# 01-POWER.net
KiCad netlist of a schematic drawn in Altium Designer
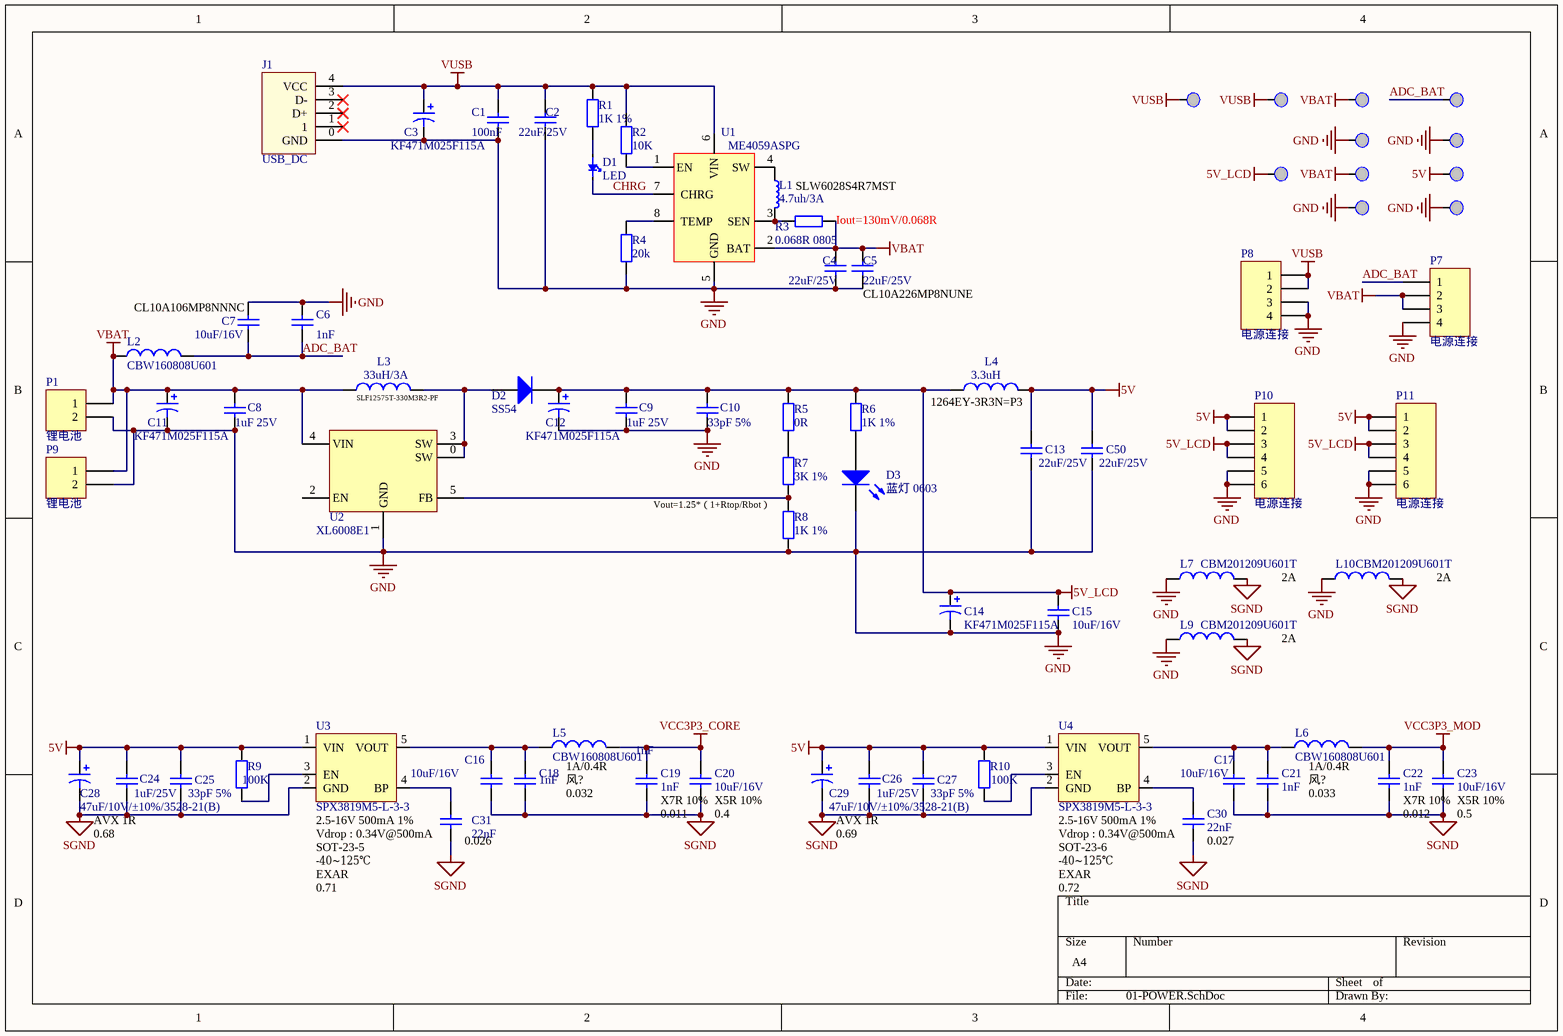
[diagram p0: 01-POWER.SchDoc]

(export (version "E")
  (design (tool "Eeschema 10.0.6"))
  (components
    (comp (ref "C1")
      (value "100nF")
      (footprint "C1608(CC0603)")
      (description "Capacitor")
      (fields (field (name "PUBLISHER") "Altium Limited"))
      (libsource (lib "Miscellaneous Devices") (part "Cap"))
    )
    (comp (ref "C2")
      (value "22uF/25V")
      (footprint "C2012(CC0805)")
      (description "Capacitor")
      (fields (field (name "PUBLISHER") "Altium Limited"))
      (libsource (lib "Miscellaneous Devices") (part "Cap"))
    )
    (comp (ref "C3")
      (value "KF471M025F115A")
      (footprint "RB.3.5/.8mm")
      (description "Polarized Capacitor (Radial)")
      (fields (field (name "PUBLISHER") "Altium Limited"))
      (libsource (lib "Miscellaneous Devices") (part "Cap Pol1"))
    )
    (comp (ref "C4")
      (value "22uF/25V")
      (footprint "C2012(CC0805)")
      (description "Capacitor")
      (fields (field (name "PUBLISHER") "Altium Limited"))
      (libsource (lib "Miscellaneous Devices") (part "Cap"))
    )
    (comp (ref "C5")
      (value "22uF/25V")
      (footprint "C2012(CC0805)")
      (description "Capacitor")
      (fields (field (name "PUBLISHER") "Altium Limited"))
      (libsource (lib "Miscellaneous Devices") (part "Cap"))
    )
    (comp (ref "C6")
      (value "1nF")
      (footprint "C1608(CC0603)")
      (description "Capacitor")
      (fields (field (name "PUBLISHER") "Altium Limited"))
      (libsource (lib "Miscellaneous Devices") (part "Cap"))
    )
    (comp (ref "C7")
      (value "10uF/16V")
      (footprint "C2012(CC0805)")
      (description "Capacitor")
      (fields (field (name "PUBLISHER") "Altium Limited"))
      (libsource (lib "Miscellaneous Devices") (part "Cap"))
    )
    (comp (ref "C8")
      (value "1uF 25V")
      (footprint "C1608(CC0603)")
      (description "Capacitor")
      (fields (field (name "PUBLISHER") "Altium Limited"))
      (libsource (lib "Miscellaneous Devices") (part "Cap"))
    )
    (comp (ref "C9")
      (value "1uF 25V")
      (footprint "C1608(CC0603)")
      (description "Capacitor")
      (fields (field (name "PUBLISHER") "Altium Limited"))
      (libsource (lib "Miscellaneous Devices") (part "Cap"))
    )
    (comp (ref "C10")
      (value "33pF 5%")
      (footprint "C1608(CC0603)")
      (description "Capacitor")
      (fields (field (name "PUBLISHER") "Altium Limited"))
      (libsource (lib "Miscellaneous Devices") (part "Cap"))
    )
    (comp (ref "C11")
      (value "KF471M025F115A")
      (footprint "RB.3.5/.8mm")
      (description "Polarized Capacitor (Radial)")
      (fields (field (name "PUBLISHER") "Altium Limited"))
      (libsource (lib "Miscellaneous Devices") (part "Cap Pol1"))
    )
    (comp (ref "C12")
      (value "KF471M025F115A")
      (footprint "RB.3.5/.8mm")
      (description "Polarized Capacitor (Radial)")
      (fields (field (name "PUBLISHER") "Altium Limited"))
      (libsource (lib "Miscellaneous Devices") (part "Cap Pol1"))
    )
    (comp (ref "C13")
      (value "22uF/25V")
      (footprint "C2012(CC0805)")
      (description "Capacitor")
      (fields (field (name "PUBLISHER") "Altium Limited"))
      (libsource (lib "Miscellaneous Devices") (part "Cap"))
    )
    (comp (ref "C14")
      (value "KF471M025F115A")
      (footprint "RB.3.5/.8mm")
      (description "Polarized Capacitor (Radial)")
      (fields (field (name "PUBLISHER") "Altium Limited"))
      (libsource (lib "Miscellaneous Devices") (part "Cap Pol1"))
    )
    (comp (ref "C15")
      (value "10uF/16V")
      (footprint "C2012(CC0805)")
      (description "Capacitor")
      (fields (field (name "PUBLISHER") "Altium Limited"))
      (libsource (lib "Miscellaneous Devices") (part "Cap"))
    )
    (comp (ref "C16")
      (value "10uF/16V")
      (footprint "C2012(CC0805)")
      (description "Capacitor")
      (fields (field (name "PUBLISHER") "Altium Limited"))
      (libsource (lib "Miscellaneous Devices") (part "Cap"))
    )
    (comp (ref "C17")
      (value "10uF/16V")
      (footprint "C2012(CC0805)")
      (description "Capacitor")
      (fields (field (name "PUBLISHER") "Altium Limited"))
      (libsource (lib "Miscellaneous Devices") (part "Cap"))
    )
    (comp (ref "C18")
      (value "1nF")
      (footprint "C1608(CC0603)")
      (description "Capacitor")
      (fields (field (name "PUBLISHER") "Altium Limited"))
      (libsource (lib "Miscellaneous Devices") (part "Cap"))
    )
    (comp (ref "C19")
      (value "1nF")
      (footprint "C1608(CC0603)")
      (description "Capacitor")
      (fields (field (name "ALTIUM_VALUE") "1nF") (field (name "PUBLISHER") "Altium Limited"))
      (libsource (lib "Miscellaneous Devices") (part "Cap"))
    )
    (comp (ref "C20")
      (value "10uF/16V")
      (footprint "C2012(CC0805)")
      (description "Capacitor")
      (fields (field (name "PUBLISHER") "Altium Limited"))
      (libsource (lib "Miscellaneous Devices") (part "Cap"))
    )
    (comp (ref "C21")
      (value "1nF")
      (footprint "C1608(CC0603)")
      (description "Capacitor")
      (fields (field (name "PUBLISHER") "Altium Limited"))
      (libsource (lib "Miscellaneous Devices") (part "Cap"))
    )
    (comp (ref "C22")
      (value "1nF")
      (footprint "C1608(CC0603)")
      (description "Capacitor")
      (fields (field (name "PUBLISHER") "Altium Limited"))
      (libsource (lib "Miscellaneous Devices") (part "Cap"))
    )
    (comp (ref "C23")
      (value "10uF/16V")
      (footprint "C2012(CC0805)")
      (description "Capacitor")
      (fields (field (name "PUBLISHER") "Altium Limited"))
      (libsource (lib "Miscellaneous Devices") (part "Cap"))
    )
    (comp (ref "C24")
      (value "1uF/25V")
      (footprint "C1608(CC0603)")
      (description "Capacitor")
      (fields (field (name "PUBLISHER") "Altium Limited"))
      (libsource (lib "Miscellaneous Devices") (part "Cap"))
    )
    (comp (ref "C25")
      (value "33pF 5%")
      (footprint "C1608(CC0603)")
      (description "Capacitor")
      (fields (field (name "PUBLISHER") "Altium Limited"))
      (libsource (lib "Miscellaneous Devices") (part "Cap"))
    )
    (comp (ref "C26")
      (value "1uF/25V")
      (footprint "C1608(CC0603)")
      (description "Capacitor")
      (fields (field (name "PUBLISHER") "Altium Limited"))
      (libsource (lib "Miscellaneous Devices") (part "Cap"))
    )
    (comp (ref "C27")
      (value "33pF 5%")
      (footprint "C1608(CC0603)")
      (description "Capacitor")
      (fields (field (name "PUBLISHER") "Altium Limited"))
      (libsource (lib "Miscellaneous Devices") (part "Cap"))
    )
    (comp (ref "C28")
      (value "47uF/10V/±10%/3528-21(B)")
      (footprint "LC-CASE-B_3528")
      (description "Polarized Capacitor (Radial)")
      (fields (field (name "PUBLISHER") "Altium Limited"))
      (libsource (lib "Miscellaneous Devices") (part "Cap Pol1"))
    )
    (comp (ref "C29")
      (value "47uF/10V/±10%/3528-21(B)")
      (footprint "LC-CASE-B_3528")
      (description "Polarized Capacitor (Radial)")
      (fields (field (name "PUBLISHER") "Altium Limited"))
      (libsource (lib "Miscellaneous Devices") (part "Cap Pol1"))
    )
    (comp (ref "C30")
      (value "22nF")
      (footprint "C1608(CC0603)")
      (description "Capacitor")
      (fields (field (name "PUBLISHER") "Altium Limited"))
      (libsource (lib "Miscellaneous Devices") (part "Cap"))
    )
    (comp (ref "C31")
      (value "22nF")
      (footprint "C1608(CC0603)")
      (description "Capacitor")
      (fields (field (name "PUBLISHER") "Altium Limited"))
      (libsource (lib "Miscellaneous Devices") (part "Cap"))
    )
    (comp (ref "C50")
      (value "22uF/25V")
      (footprint "C2012(CC0805)")
      (description "Capacitor")
      (fields (field (name "PUBLISHER") "Altium Limited"))
      (libsource (lib "Miscellaneous Devices") (part "Cap"))
    )
    (comp (ref "D1") (value "LED") (footprint "LC-0805_LED_S1") (libsource (lib "个人") (part "LED")))
    (comp (ref "D2")
      (value "SS54")
      (footprint "LC-SMA(DO-214AC)_S5")
      (description "二极管")
      (libsource (lib "Miscellaneous Devices LC") (part "SMA(DO-214AC) M7"))
    )
    (comp (ref "D3")
      (value "蓝灯 0603")
      (footprint "LC-0603_LED_S1")
      (description "发光二极管")
      (libsource (lib "Miscellaneous Devices LC") (part "0603 蓝灯"))
    )
    (comp (ref "J1") (value "USB_DC") (footprint "USB_DC") (libsource (lib "个人") (part "USB_DC")))
    (comp (ref "L1")
      (value "4.7uh/3A")
      (footprint "IND60X60")
      (description "电感")
      (libsource (lib "个人") (part "电感"))
    )
    (comp (ref "L2")
      (value "CBW160808U601")
      (footprint "C1608(CC0603)")
      (description "Inductor")
      (fields (field (name "PUBLISHER") "Altium Limited"))
      (libsource (lib "Miscellaneous Devices") (part "Inductor"))
    )
    (comp (ref "L3")
      (value "33uH/3A")
      (footprint "IND125x125")
      (description "Inductor")
      (fields (field (name "PUBLISHER") "Altium Limited"))
      (libsource (lib "Miscellaneous Devices") (part "Inductor"))
    )
    (comp (ref "L4")
      (value "3.3uH")
      (footprint "IND60X60")
      (description "Inductor")
      (fields (field (name "PUBLISHER") "Altium Limited"))
      (libsource (lib "Miscellaneous Devices") (part "Inductor"))
    )
    (comp (ref "L5")
      (value "CBW160808U601")
      (footprint "C1608(CC0603)")
      (description "Inductor")
      (fields (field (name "PUBLISHER") "Altium Limited"))
      (libsource (lib "Miscellaneous Devices") (part "Inductor"))
    )
    (comp (ref "L6")
      (value "CBW160808U601")
      (footprint "C1608(CC0603)")
      (description "Inductor")
      (fields (field (name "PUBLISHER") "Altium Limited"))
      (libsource (lib "Miscellaneous Devices") (part "Inductor"))
    )
    (comp (ref "L7")
      (value "CBM201209U601T")
      (footprint "C2012(CC0805)")
      (description "Inductor")
      (fields (field (name "PUBLISHER") "Altium Limited"))
      (libsource (lib "Miscellaneous Devices") (part "Inductor"))
    )
    (comp (ref "L9")
      (value "CBM201209U601T")
      (footprint "C2012(CC0805)")
      (description "Inductor")
      (fields (field (name "PUBLISHER") "Altium Limited"))
      (libsource (lib "Miscellaneous Devices") (part "Inductor"))
    )
    (comp (ref "L10")
      (value "CBM201209U601T")
      (footprint "C2012(CC0805)")
      (description "Inductor")
      (fields (field (name "PUBLISHER") "Altium Limited"))
      (libsource (lib "Miscellaneous Devices") (part "Inductor"))
    )
    (comp (ref "P1")
      (value "锂电池")
      (footprint "XH2.54-2A")
      (description "Header, 2-Pin")
      (fields (field (name "PUBLISHER") "Altium Limited"))
      (libsource (lib "Miscellaneous Connectors") (part "Header 2"))
    )
    (comp (ref "P7")
      (value "电源连接")
      (footprint "HDR1X4")
      (description "Header, 4-Pin")
      (fields (field (name "PUBLISHER") "Altium Limited"))
      (libsource (lib "") (part "Header 4_1"))
    )
    (comp (ref "P8")
      (value "电源连接")
      (footprint "HDR1X4")
      (description "Header, 4-Pin")
      (fields (field (name "PUBLISHER") "Altium Limited"))
      (libsource (lib "Miscellaneous Connectors") (part "Header 4"))
    )
    (comp (ref "P9")
      (value "锂电池")
      (footprint "XH2.54-2A")
      (description "Header, 2-Pin")
      (fields (field (name "PUBLISHER") "Altium Limited"))
      (libsource (lib "Miscellaneous Connectors") (part "Header 2"))
    )
    (comp (ref "P10")
      (value "电源连接")
      (footprint "HDR1X6")
      (description "Header, 6-Pin")
      (fields (field (name "PUBLISHER") "Altium Limited"))
      (libsource (lib "Miscellaneous Connectors") (part "Header 6"))
    )
    (comp (ref "P11")
      (value "电源连接")
      (footprint "HDR1X6")
      (description "Header, 6-Pin")
      (fields (field (name "PUBLISHER") "Altium Limited"))
      (libsource (lib "Miscellaneous Connectors") (part "Header 6"))
    )
    (comp (ref "R1")
      (value "1K 1%")
      (footprint "C1608(CC0603)")
      (description "Resistor")
      (fields (field (name "PUBLISHER") "Altium Limited"))
      (libsource (lib "Miscellaneous Devices") (part "Res2"))
    )
    (comp (ref "R2")
      (value "10K")
      (footprint "C1608(CC0603)")
      (description "Resistor")
      (fields (field (name "PUBLISHER") "Altium Limited"))
      (libsource (lib "Miscellaneous Devices") (part "Res2"))
    )
    (comp (ref "R3")
      (value "0.068R 0805")
      (footprint "C2012(CC0805)")
      (description "Resistor")
      (fields (field (name "PUBLISHER") "Altium Limited"))
      (libsource (lib "") (part "Res2_2"))
    )
    (comp (ref "R4")
      (value "20k")
      (footprint "C1608(CC0603)")
      (description "Resistor")
      (fields (field (name "PUBLISHER") "Altium Limited"))
      (libsource (lib "Miscellaneous Devices") (part "Res2"))
    )
    (comp (ref "R5")
      (value "0R")
      (footprint "C1608(CC0603)")
      (description "Resistor")
      (fields (field (name "PUBLISHER") "Altium Limited"))
      (libsource (lib "") (part "Res2_1"))
    )
    (comp (ref "R6")
      (value "1K 1%")
      (footprint "C1608(CC0603)")
      (description "Resistor")
      (fields (field (name "PUBLISHER") "Altium Limited"))
      (libsource (lib "") (part "Res2_1"))
    )
    (comp (ref "R7")
      (value "3K 1%")
      (footprint "C1608(CC0603)")
      (description "Resistor")
      (fields (field (name "PUBLISHER") "Altium Limited"))
      (libsource (lib "") (part "Res2_1"))
    )
    (comp (ref "R8")
      (value "1K 1%")
      (footprint "C1608(CC0603)")
      (description "Resistor")
      (fields (field (name "PUBLISHER") "Altium Limited"))
      (libsource (lib "") (part "Res2_1"))
    )
    (comp (ref "R9")
      (value "100K")
      (footprint "C1608(CC0603)")
      (description "Resistor")
      (fields (field (name "PUBLISHER") "Altium Limited"))
      (libsource (lib "Miscellaneous Devices") (part "Res2"))
    )
    (comp (ref "R10")
      (value "100K")
      (footprint "C1608(CC0603)")
      (description "Resistor")
      (fields (field (name "PUBLISHER") "Altium Limited"))
      (libsource (lib "Miscellaneous Devices") (part "Res2"))
    )
    (comp (ref "T1") (value "TP") (footprint "M2铜柱") (libsource (lib "个人") (part "TP")))
    (comp (ref "T2") (value "TP") (footprint "M2铜柱") (libsource (lib "个人") (part "TP")))
    (comp (ref "T3") (value "TP") (footprint "M2铜柱") (libsource (lib "个人") (part "TP")))
    (comp (ref "T4") (value "TP") (footprint "M2铜柱") (libsource (lib "个人") (part "TP")))
    (comp (ref "T5") (value "TP") (footprint "M2铜柱") (libsource (lib "个人") (part "TP")))
    (comp (ref "T6") (value "TP") (footprint "M2铜柱") (libsource (lib "个人") (part "TP")))
    (comp (ref "T7") (value "TP") (footprint "M2铜柱") (libsource (lib "个人") (part "TP")))
    (comp (ref "T8") (value "TP") (footprint "M2铜柱") (libsource (lib "个人") (part "TP")))
    (comp (ref "T9") (value "TP") (footprint "M2铜柱") (libsource (lib "个人") (part "TP")))
    (comp (ref "T10") (value "TP") (footprint "M2铜柱") (libsource (lib "个人") (part "TP")))
    (comp (ref "T11") (value "TP") (footprint "M2铜柱") (libsource (lib "个人") (part "TP")))
    (comp (ref "U1")
      (value "ME4059ASPG")
      (footprint "LC-SOP-8_EP_150mil")
      (description "4.2v/2A")
      (libsource (lib "个人") (part "ME4059"))
    )
    (comp (ref "U2") (value "XL6008E1") (footprint "LC-TO-252-5") (libsource (lib "个人") (part "XL6008E1")))
    (comp (ref "U3")
      (value "SPX3819M5-L-3-3")
      (footprint "SOT-23-5")
      (libsource (lib "Schlibsxw") (part "RT9193"))
    )
    (comp (ref "U4")
      (value "SPX3819M5-L-3-3")
      (footprint "SOT-23-5")
      (libsource (lib "Schlibsxw") (part "RT9193"))
    )
  )
  (nets
    (net (code "1") (name "/ADC_BAT") (class "Default")
      (node (ref "C6") (pin "1") (pinfunction "1_1") (pintype "passive"))
      (node (ref "C7") (pin "1") (pinfunction "1_1") (pintype "passive"))
      (node (ref "L2") (pin "2") (pinfunction "2_2") (pintype "passive"))
      (node (ref "P7") (pin "1") (pinfunction "1_1") (pintype "passive"))
      (node (ref "T3") (pin "1") (pintype "passive"))
    )
    (net (code "2") (name "/CHRG") (class "Default")
      (node (ref "D1") (pin "K") (pinfunction "K_K") (pintype "passive"))
      (node (ref "U1") (pin "7") (pinfunction "CHRG_7") (pintype "passive"))
    )
    (net (code "3") (name "5V") (class "Default")
      (node (ref "C13") (pin "2") (pinfunction "2_2") (pintype "passive"))
      (node (ref "C24") (pin "1") (pinfunction "1_1") (pintype "passive"))
      (node (ref "C25") (pin "2") (pinfunction "2_2") (pintype "passive"))
      (node (ref "C26") (pin "1") (pinfunction "1_1") (pintype "passive"))
      (node (ref "C27") (pin "2") (pinfunction "2_2") (pintype "passive"))
      (node (ref "C28") (pin "1") (pinfunction "1_1") (pintype "passive"))
      (node (ref "C29") (pin "1") (pinfunction "1_1") (pintype "passive"))
      (node (ref "C50") (pin "2") (pinfunction "2_2") (pintype "passive"))
      (node (ref "L4") (pin "2") (pinfunction "2_2") (pintype "passive"))
      (node (ref "P10") (pin "1") (pinfunction "1_1") (pintype "passive"))
      (node (ref "P10") (pin "2") (pinfunction "2_2") (pintype "passive"))
      (node (ref "P11") (pin "1") (pinfunction "1_1") (pintype "passive"))
      (node (ref "P11") (pin "2") (pinfunction "2_2") (pintype "passive"))
      (node (ref "R10") (pin "1") (pinfunction "1_1") (pintype "passive"))
      (node (ref "R9") (pin "1") (pinfunction "1_1") (pintype "passive"))
      (node (ref "T9") (pin "1") (pintype "passive"))
      (node (ref "U3") (pin "1") (pinfunction "VIN_1") (pintype "passive"))
      (node (ref "U4") (pin "1") (pinfunction "VIN_1") (pintype "passive"))
    )
    (net (code "4") (name "5V_LCD") (class "Default")
      (node (ref "C10") (pin "1") (pinfunction "1_1") (pintype "passive"))
      (node (ref "C12") (pin "1") (pinfunction "1_1") (pintype "passive"))
      (node (ref "C14") (pin "1") (pinfunction "1_1") (pintype "passive"))
      (node (ref "C15") (pin "2") (pinfunction "2_2") (pintype "passive"))
      (node (ref "C9") (pin "1") (pinfunction "1_1") (pintype "passive"))
      (node (ref "D2") (pin "2") (pinfunction "K_2") (pintype "passive"))
      (node (ref "L4") (pin "1") (pinfunction "1_1") (pintype "passive"))
      (node (ref "P10") (pin "3") (pinfunction "3_3") (pintype "passive"))
      (node (ref "P10") (pin "4") (pinfunction "4_4") (pintype "passive"))
      (node (ref "P11") (pin "3") (pinfunction "3_3") (pintype "passive"))
      (node (ref "P11") (pin "4") (pinfunction "4_4") (pintype "passive"))
      (node (ref "R5") (pin "2") (pinfunction "2_2") (pintype "passive"))
      (node (ref "R6") (pin "2") (pinfunction "2_2") (pintype "passive"))
      (node (ref "T10") (pin "1") (pintype "passive"))
    )
    (net (code "5") (name "GND") (class "Default")
      (node (ref "C1") (pin "1") (pinfunction "1_1") (pintype "passive"))
      (node (ref "C10") (pin "2") (pinfunction "2_2") (pintype "passive"))
      (node (ref "C11") (pin "2") (pinfunction "2_2") (pintype "passive"))
      (node (ref "C12") (pin "2") (pinfunction "2_2") (pintype "passive"))
      (node (ref "C13") (pin "1") (pinfunction "1_1") (pintype "passive"))
      (node (ref "C14") (pin "2") (pinfunction "2_2") (pintype "passive"))
      (node (ref "C15") (pin "1") (pinfunction "1_1") (pintype "passive"))
      (node (ref "C2") (pin "1") (pinfunction "1_1") (pintype "passive"))
      (node (ref "C3") (pin "2") (pinfunction "2_2") (pintype "passive"))
      (node (ref "C4") (pin "1") (pinfunction "1_1") (pintype "passive"))
      (node (ref "C5") (pin "1") (pinfunction "1_1") (pintype "passive"))
      (node (ref "C50") (pin "1") (pinfunction "1_1") (pintype "passive"))
      (node (ref "C6") (pin "2") (pinfunction "2_2") (pintype "passive"))
      (node (ref "C7") (pin "2") (pinfunction "2_2") (pintype "passive"))
      (node (ref "C8") (pin "2") (pinfunction "2_2") (pintype "passive"))
      (node (ref "C9") (pin "2") (pinfunction "2_2") (pintype "passive"))
      (node (ref "D3") (pin "K") (pinfunction "K_K") (pintype "passive"))
      (node (ref "J1") (pin "0") (pinfunction "GND_0") (pintype "passive"))
      (node (ref "L10") (pin "1") (pinfunction "1_1") (pintype "passive"))
      (node (ref "L7") (pin "1") (pinfunction "1_1") (pintype "passive"))
      (node (ref "L9") (pin "1") (pinfunction "1_1") (pintype "passive"))
      (node (ref "P1") (pin "2") (pinfunction "2_2") (pintype "passive"))
      (node (ref "P10") (pin "5") (pinfunction "5_5") (pintype "passive"))
      (node (ref "P10") (pin "6") (pinfunction "6_6") (pintype "passive"))
      (node (ref "P11") (pin "5") (pinfunction "5_5") (pintype "passive"))
      (node (ref "P11") (pin "6") (pinfunction "6_6") (pintype "passive"))
      (node (ref "P7") (pin "4") (pinfunction "4_4") (pintype "passive"))
      (node (ref "P8") (pin "3") (pinfunction "3_3") (pintype "passive"))
      (node (ref "P8") (pin "4") (pinfunction "4_4") (pintype "passive"))
      (node (ref "P9") (pin "2") (pinfunction "2_2") (pintype "passive"))
      (node (ref "R4") (pin "2") (pinfunction "2_2") (pintype "passive"))
      (node (ref "R8") (pin "1") (pinfunction "1_1") (pintype "passive"))
      (node (ref "T2") (pin "1") (pintype "passive"))
      (node (ref "T4") (pin "1") (pintype "passive"))
      (node (ref "T6") (pin "1") (pintype "passive"))
      (node (ref "T7") (pin "1") (pintype "passive"))
      (node (ref "U1") (pin "5") (pinfunction "GND_5") (pintype "passive"))
      (node (ref "U2") (pin "1") (pinfunction "GND_1") (pintype "passive"))
    )
    (net (code "6") (name "Net-(D1-PadA)") (class "Default")
      (node (ref "D1") (pin "A") (pinfunction "A_A") (pintype "passive"))
      (node (ref "R1") (pin "2") (pinfunction "2_2") (pintype "passive"))
    )
    (net (code "7") (name "Net-(D2-A)") (class "Default")
      (node (ref "D2") (pin "1") (pinfunction "A_1") (pintype "passive"))
      (node (ref "L3") (pin "2") (pinfunction "2_2") (pintype "passive"))
      (node (ref "U2") (pin "0") (pinfunction "SW_0") (pintype "passive"))
      (node (ref "U2") (pin "3") (pinfunction "SW_3") (pintype "passive"))
    )
    (net (code "8") (name "Net-(D3-PadA)") (class "Default")
      (node (ref "D3") (pin "A") (pinfunction "A_A") (pintype "passive"))
      (node (ref "R6") (pin "1") (pinfunction "1_1") (pintype "passive"))
    )
    (net (code "9") (name "Net-(R5-Pad1)") (class "Default")
      (node (ref "R5") (pin "1") (pinfunction "1_1") (pintype "passive"))
      (node (ref "R7") (pin "2") (pinfunction "2_2") (pintype "passive"))
    )
    (net (code "10") (name "Net-(U1-EN)") (class "Default")
      (node (ref "R2") (pin "2") (pinfunction "2_2") (pintype "passive"))
      (node (ref "U1") (pin "1") (pinfunction "EN_1") (pintype "passive"))
    )
    (net (code "11") (name "Net-(U1-SEN)") (class "Default")
      (node (ref "L1") (pin "2") (pintype "passive"))
      (node (ref "R3") (pin "2") (pinfunction "2_2") (pintype "passive"))
      (node (ref "U1") (pin "3") (pinfunction "SEN_3") (pintype "passive"))
    )
    (net (code "12") (name "Net-(U1-SW)") (class "Default")
      (node (ref "L1") (pin "1") (pintype "passive"))
      (node (ref "U1") (pin "4") (pinfunction "SW_4") (pintype "passive"))
    )
    (net (code "13") (name "Net-(U1-TEMP)") (class "Default")
      (node (ref "R4") (pin "1") (pinfunction "1_1") (pintype "passive"))
      (node (ref "U1") (pin "8") (pinfunction "TEMP_8") (pintype "passive"))
    )
    (net (code "14") (name "Net-(U2-FB)") (class "Default")
      (node (ref "R7") (pin "1") (pinfunction "1_1") (pintype "passive"))
      (node (ref "R8") (pin "2") (pinfunction "2_2") (pintype "passive"))
      (node (ref "U2") (pin "5") (pinfunction "FB_5") (pintype "passive"))
    )
    (net (code "15") (name "Net-(U3-BP)") (class "Default")
      (node (ref "C31") (pin "2") (pinfunction "2_2") (pintype "passive"))
      (node (ref "U3") (pin "4") (pinfunction "BP_4") (pintype "passive"))
    )
    (net (code "16") (name "Net-(U3-EN)") (class "Default")
      (node (ref "R9") (pin "2") (pinfunction "2_2") (pintype "passive"))
      (node (ref "U3") (pin "3") (pinfunction "EN_3") (pintype "passive"))
    )
    (net (code "17") (name "Net-(U3-VOUT)") (class "Default")
      (node (ref "C16") (pin "2") (pinfunction "2_2") (pintype "passive"))
      (node (ref "C18") (pin "2") (pinfunction "2_2") (pintype "passive"))
      (node (ref "L5") (pin "1") (pinfunction "1_1") (pintype "passive"))
      (node (ref "U3") (pin "5") (pinfunction "VOUT_5") (pintype "passive"))
    )
    (net (code "18") (name "Net-(U4-BP)") (class "Default")
      (node (ref "C30") (pin "2") (pinfunction "2_2") (pintype "passive"))
      (node (ref "U4") (pin "4") (pinfunction "BP_4") (pintype "passive"))
    )
    (net (code "19") (name "Net-(U4-EN)") (class "Default")
      (node (ref "R10") (pin "2") (pinfunction "2_2") (pintype "passive"))
      (node (ref "U4") (pin "3") (pinfunction "EN_3") (pintype "passive"))
    )
    (net (code "20") (name "Net-(U4-VOUT)") (class "Default")
      (node (ref "C17") (pin "2") (pinfunction "2_2") (pintype "passive"))
      (node (ref "C21") (pin "2") (pinfunction "2_2") (pintype "passive"))
      (node (ref "L6") (pin "1") (pinfunction "1_1") (pintype "passive"))
      (node (ref "U4") (pin "5") (pinfunction "VOUT_5") (pintype "passive"))
    )
    (net (code "21") (name "SGND") (class "Default")
      (node (ref "C16") (pin "1") (pinfunction "1_1") (pintype "passive"))
      (node (ref "C17") (pin "1") (pinfunction "1_1") (pintype "passive"))
      (node (ref "C18") (pin "1") (pinfunction "1_1") (pintype "passive"))
      (node (ref "C19") (pin "1") (pinfunction "1_1") (pintype "passive"))
      (node (ref "C20") (pin "1") (pinfunction "1_1") (pintype "passive"))
      (node (ref "C21") (pin "1") (pinfunction "1_1") (pintype "passive"))
      (node (ref "C22") (pin "1") (pinfunction "1_1") (pintype "passive"))
      (node (ref "C23") (pin "1") (pinfunction "1_1") (pintype "passive"))
      (node (ref "C24") (pin "2") (pinfunction "2_2") (pintype "passive"))
      (node (ref "C25") (pin "1") (pinfunction "1_1") (pintype "passive"))
      (node (ref "C26") (pin "2") (pinfunction "2_2") (pintype "passive"))
      (node (ref "C27") (pin "1") (pinfunction "1_1") (pintype "passive"))
      (node (ref "C28") (pin "2") (pinfunction "2_2") (pintype "passive"))
      (node (ref "C29") (pin "2") (pinfunction "2_2") (pintype "passive"))
      (node (ref "C30") (pin "1") (pinfunction "1_1") (pintype "passive"))
      (node (ref "C31") (pin "1") (pinfunction "1_1") (pintype "passive"))
      (node (ref "L10") (pin "2") (pinfunction "2_2") (pintype "passive"))
      (node (ref "L7") (pin "2") (pinfunction "2_2") (pintype "passive"))
      (node (ref "L9") (pin "2") (pinfunction "2_2") (pintype "passive"))
      (node (ref "U3") (pin "2") (pinfunction "GND_2") (pintype "passive"))
      (node (ref "U4") (pin "2") (pinfunction "GND_2") (pintype "passive"))
    )
    (net (code "22") (name "VBAT") (class "Default")
      (node (ref "C11") (pin "1") (pinfunction "1_1") (pintype "passive"))
      (node (ref "C4") (pin "2") (pinfunction "2_2") (pintype "passive"))
      (node (ref "C5") (pin "2") (pinfunction "2_2") (pintype "passive"))
      (node (ref "C8") (pin "1") (pinfunction "1_1") (pintype "passive"))
      (node (ref "L2") (pin "1") (pinfunction "1_1") (pintype "passive"))
      (node (ref "L3") (pin "1") (pinfunction "1_1") (pintype "passive"))
      (node (ref "P1") (pin "1") (pinfunction "1_1") (pintype "passive"))
      (node (ref "P7") (pin "2") (pinfunction "2_2") (pintype "passive"))
      (node (ref "P7") (pin "3") (pinfunction "3_3") (pintype "passive"))
      (node (ref "P9") (pin "1") (pinfunction "1_1") (pintype "passive"))
      (node (ref "R3") (pin "1") (pinfunction "1_1") (pintype "passive"))
      (node (ref "T5") (pin "1") (pintype "passive"))
      (node (ref "T8") (pin "1") (pintype "passive"))
      (node (ref "U1") (pin "2") (pinfunction "BAT_2") (pintype "passive"))
      (node (ref "U2") (pin "4") (pinfunction "VIN_4") (pintype "passive"))
    )
    (net (code "23") (name "VCC3P3_CORE") (class "Default")
      (node (ref "C19") (pin "2") (pinfunction "2_2") (pintype "passive"))
      (node (ref "C20") (pin "2") (pinfunction "2_2") (pintype "passive"))
      (node (ref "L5") (pin "2") (pinfunction "2_2") (pintype "passive"))
    )
    (net (code "24") (name "VCC3P3_MOD") (class "Default")
      (node (ref "C22") (pin "2") (pinfunction "2_2") (pintype "passive"))
      (node (ref "C23") (pin "2") (pinfunction "2_2") (pintype "passive"))
      (node (ref "L6") (pin "2") (pinfunction "2_2") (pintype "passive"))
    )
    (net (code "25") (name "VUSB") (class "Default")
      (node (ref "C1") (pin "2") (pinfunction "2_2") (pintype "passive"))
      (node (ref "C2") (pin "2") (pinfunction "2_2") (pintype "passive"))
      (node (ref "C3") (pin "1") (pinfunction "1_1") (pintype "passive"))
      (node (ref "J1") (pin "4") (pinfunction "VCC_4") (pintype "passive"))
      (node (ref "P8") (pin "1") (pinfunction "1_1") (pintype "passive"))
      (node (ref "P8") (pin "2") (pinfunction "2_2") (pintype "passive"))
      (node (ref "R1") (pin "1") (pinfunction "1_1") (pintype "passive"))
      (node (ref "R2") (pin "1") (pinfunction "1_1") (pintype "passive"))
      (node (ref "T1") (pin "1") (pintype "passive"))
      (node (ref "T11") (pin "1") (pintype "passive"))
      (node (ref "U1") (pin "6") (pinfunction "VIN_6") (pintype "passive"))
    )
    (net (code "26") (name "unconnected-(J1-D+-Pad2)") (class "Default")
      (node (ref "J1") (pin "2") (pinfunction "D+_2") (pintype "passive+no_connect"))
    )
    (net (code "27") (name "unconnected-(J1-D--Pad3)") (class "Default")
      (node (ref "J1") (pin "3") (pinfunction "D-_3") (pintype "passive+no_connect"))
    )
    (net (code "28") (name "unconnected-(J1-Pad1)") (class "Default")
      (node (ref "J1") (pin "1") (pinfunction "1_1") (pintype "passive+no_connect"))
    )
    (net (code "29") (name "unconnected-(U2-EN-Pad2)") (class "Default")
      (node (ref "U2") (pin "2") (pinfunction "EN_2") (pintype "passive"))
    )
  )
)
